# Adafruit_RGB_Matrix_HAT.net
KiCad netlist of a schematic drawn in EAGLE
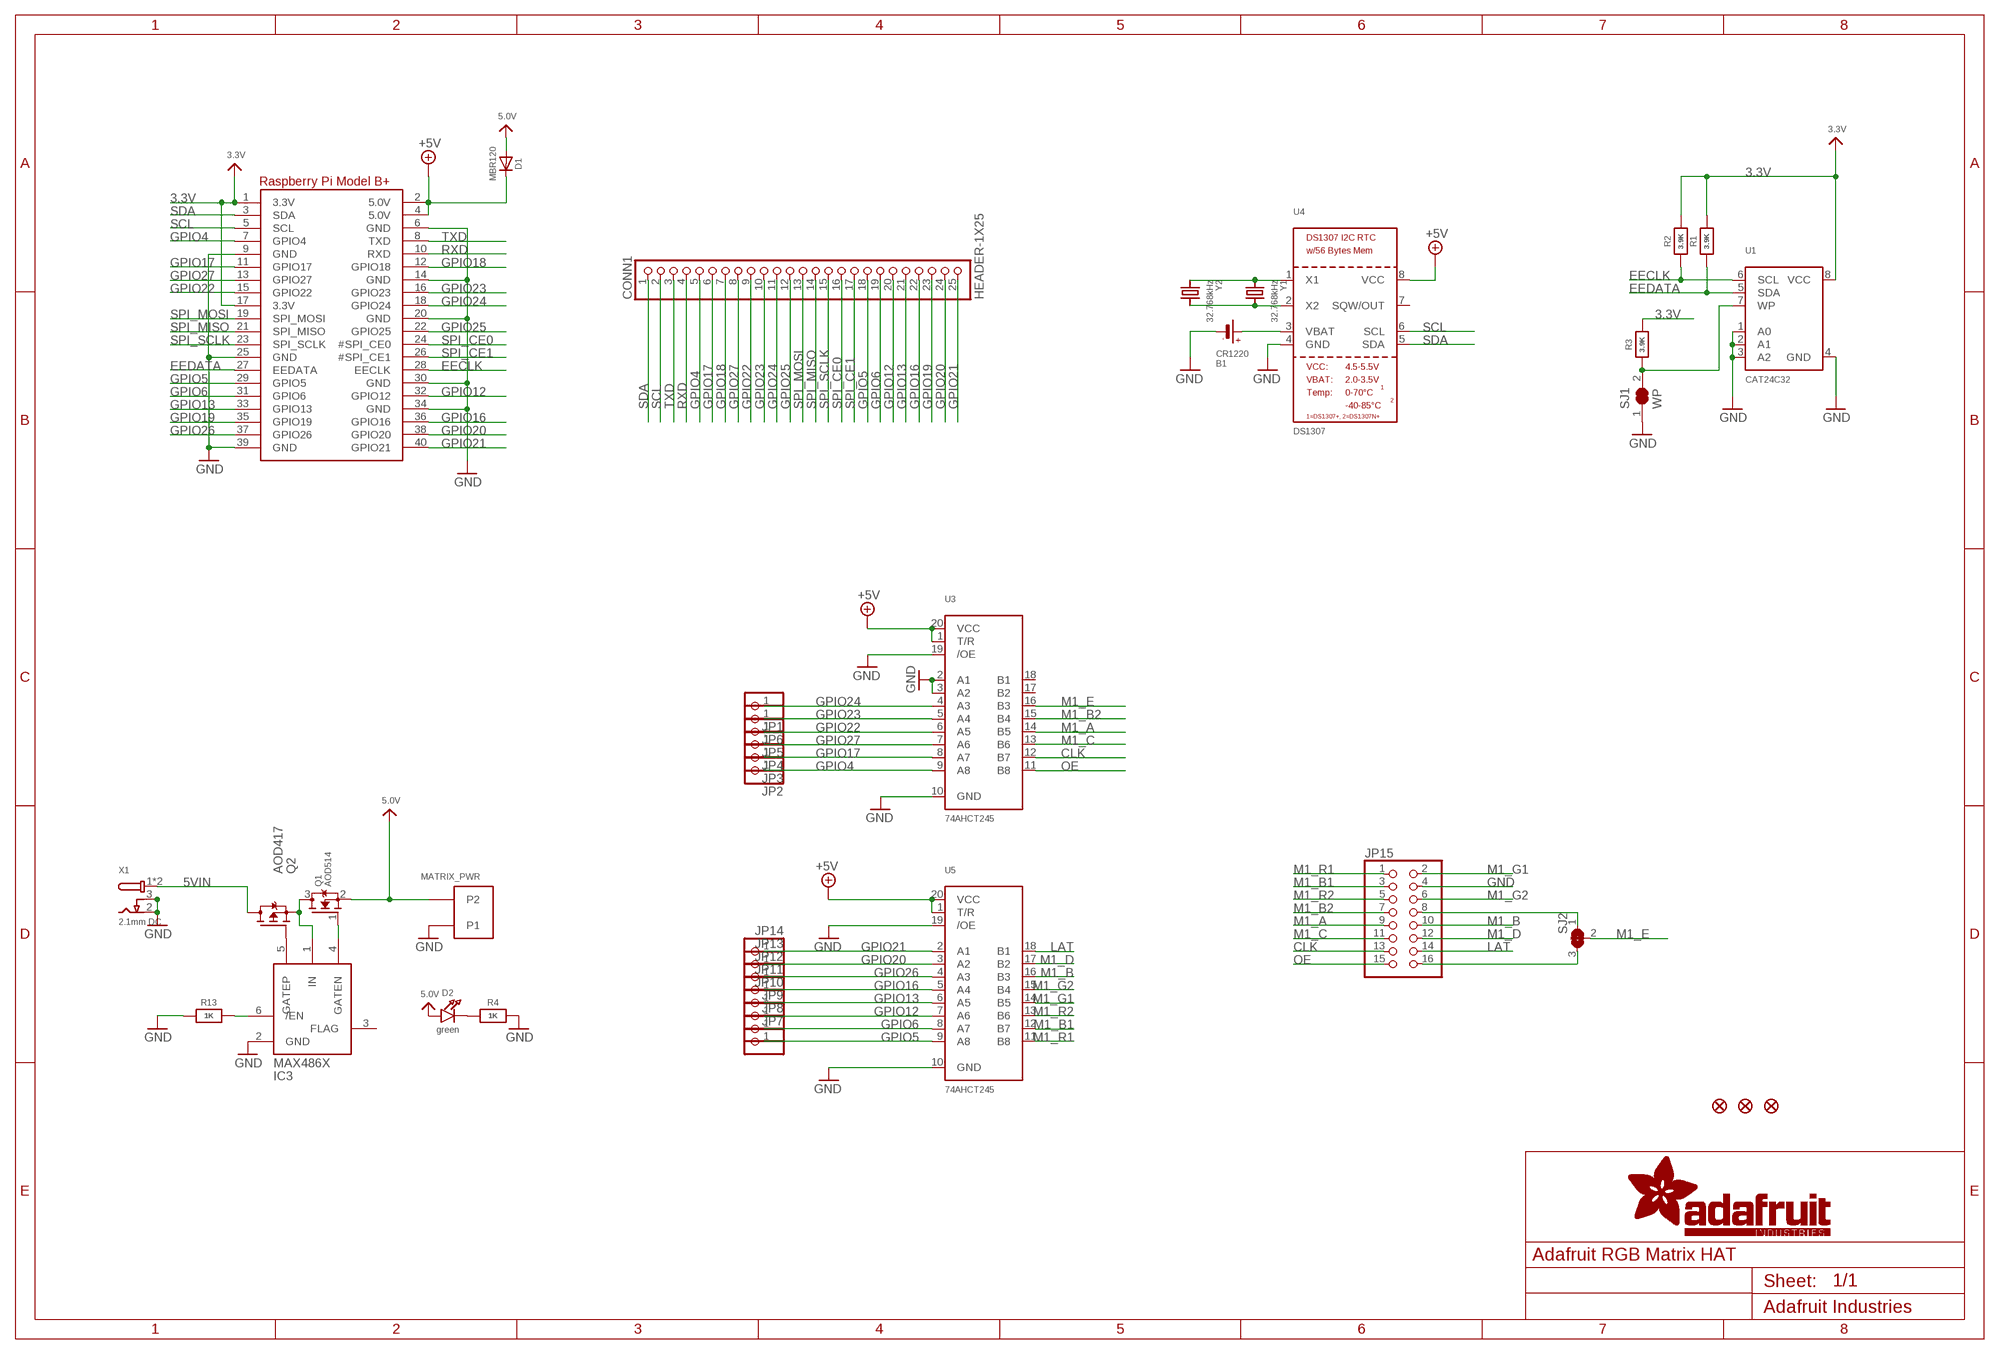
[diagram p0: schematic, sheet 1]

(export (version "E")
  (design (tool "Eeschema 10.0.6"))
  (components
    (comp (ref "B1")
      (value "CR1220")
      (footprint "eagle-import:CR1220")
      (libsource (lib "eagle-import") (part "BATTERYCR1220_SMT"))
    )
    (comp (ref "CONN1")
      (value "HEADER-1X25")
      (footprint "eagle-import:1X25_ROUND_70MIL")
      (libsource (lib "eagle-import") (part "HEADER-1X25"))
    )
    (comp (ref "D1")
      (value "MBR120")
      (footprint "eagle-import:SOD-123")
      (libsource (lib "eagle-import") (part "DIODESOD-123"))
    )
    (comp (ref "D2")
      (value "green")
      (footprint "eagle-import:CHIPLED_0805_NOOUTLINE")
      (libsource (lib "eagle-import") (part "LED0805_NOOUTLINE"))
    )
    (comp (ref "FID1")
      (value "FIDUCIAL_1MM")
      (footprint "eagle-import:FIDUCIAL_1MM")
      (libsource (lib "eagle-import") (part "FIDUCIAL_1MM"))
    )
    (comp (ref "FID2")
      (value "FIDUCIAL_1MM")
      (footprint "eagle-import:FIDUCIAL_1MM")
      (libsource (lib "eagle-import") (part "FIDUCIAL_1MM"))
    )
    (comp (ref "FID3")
      (value "FIDUCIAL_1MM")
      (footprint "eagle-import:FIDUCIAL_1MM")
      (libsource (lib "eagle-import") (part "FIDUCIAL_1MM"))
    )
    (comp (ref "IC3")
      (value "MAX4866T")
      (footprint "eagle-import:SOT23-6")
      (libsource (lib "eagle-import") (part "MAX486X/SOT"))
    )
    (comp (ref "JP1")
      (value "PINHD-1X1")
      (footprint "eagle-import:1X01")
      (libsource (lib "eagle-import") (part "PINHD-1X1"))
    )
    (comp (ref "JP2")
      (value "PINHD-1X1")
      (footprint "eagle-import:1X01")
      (libsource (lib "eagle-import") (part "PINHD-1X1"))
    )
    (comp (ref "JP3")
      (value "PINHD-1X1")
      (footprint "eagle-import:1X01")
      (libsource (lib "eagle-import") (part "PINHD-1X1"))
    )
    (comp (ref "JP4")
      (value "PINHD-1X1")
      (footprint "eagle-import:1X01")
      (libsource (lib "eagle-import") (part "PINHD-1X1"))
    )
    (comp (ref "JP5")
      (value "PINHD-1X1")
      (footprint "eagle-import:1X01")
      (libsource (lib "eagle-import") (part "PINHD-1X1"))
    )
    (comp (ref "JP6")
      (value "PINHD-1X1")
      (footprint "eagle-import:1X01")
      (libsource (lib "eagle-import") (part "PINHD-1X1"))
    )
    (comp (ref "JP7")
      (value "PINHD-1X1")
      (footprint "eagle-import:1X01")
      (libsource (lib "eagle-import") (part "PINHD-1X1"))
    )
    (comp (ref "JP8")
      (value "PINHD-1X1")
      (footprint "eagle-import:1X01")
      (libsource (lib "eagle-import") (part "PINHD-1X1"))
    )
    (comp (ref "JP9")
      (value "PINHD-1X1")
      (footprint "eagle-import:1X01")
      (libsource (lib "eagle-import") (part "PINHD-1X1"))
    )
    (comp (ref "JP10")
      (value "PINHD-1X1")
      (footprint "eagle-import:1X01")
      (libsource (lib "eagle-import") (part "PINHD-1X1"))
    )
    (comp (ref "JP11")
      (value "PINHD-1X1")
      (footprint "eagle-import:1X01")
      (libsource (lib "eagle-import") (part "PINHD-1X1"))
    )
    (comp (ref "JP12")
      (value "PINHD-1X1")
      (footprint "eagle-import:1X01")
      (libsource (lib "eagle-import") (part "PINHD-1X1"))
    )
    (comp (ref "JP13")
      (value "PINHD-1X1")
      (footprint "eagle-import:1X01")
      (libsource (lib "eagle-import") (part "PINHD-1X1"))
    )
    (comp (ref "JP14")
      (value "PINHD-1X1")
      (footprint "eagle-import:1X01")
      (libsource (lib "eagle-import") (part "PINHD-1X1"))
    )
    (comp (ref "JP15")
      (value "HEADER-2X8_SHROUDED")
      (footprint "eagle-import:2X08_SHROUDED")
      (libsource (lib "eagle-import") (part "HEADER-2X8_SHROUDED"))
    )
    (comp (ref "MATRIX_PWR")
      (value "PINHEAD")
      (footprint "eagle-import:TERMBLOCK508")
      (libsource (lib "eagle-import") (part "PINHEAD"))
    )
    (comp (ref "Q1")
      (value "AOD514")
      (footprint "eagle-import:TO252")
      (libsource (lib "eagle-import") (part "MOSFET-N_TO252"))
    )
    (comp (ref "Q2")
      (value "AOD417")
      (footprint "eagle-import:TO252")
      (libsource (lib "eagle-import") (part "MOSFET-PTO252"))
    )
    (comp (ref "R1")
      (value "3.9K")
      (footprint "eagle-import:0805-NO")
      (libsource (lib "eagle-import") (part "RESISTOR0805_NOOUTLINE"))
    )
    (comp (ref "R2")
      (value "3.9K")
      (footprint "eagle-import:0805-NO")
      (libsource (lib "eagle-import") (part "RESISTOR0805_NOOUTLINE"))
    )
    (comp (ref "R3")
      (value "3.9K")
      (footprint "eagle-import:0805-NO")
      (libsource (lib "eagle-import") (part "RESISTOR0805_NOOUTLINE"))
    )
    (comp (ref "R4")
      (value "1K")
      (footprint "eagle-import:0805-NO")
      (libsource (lib "eagle-import") (part "RESISTOR0805_NOOUTLINE"))
    )
    (comp (ref "R13")
      (value "1K")
      (footprint "eagle-import:0805-NO")
      (libsource (lib "eagle-import") (part "RESISTOR0805_NOOUTLINE"))
    )
    (comp (ref "RPI1")
      (value "RASPBERRYPI_BPLUS_HATSLOTS")
      (footprint "eagle-import:PI_HAT_SLOTS")
      (libsource (lib "eagle-import") (part "RASPBERRYPI_BPLUS_HATSLOTS"))
    )
    (comp (ref "SJ1")
      (value "WP")
      (footprint "eagle-import:SOLDERJUMPER_CLOSEDWIRE")
      (libsource (lib "eagle-import") (part "SOLDERJUMPER_CLOSED"))
    )
    (comp (ref "SJ2")
      (value "SOLDERJUMPER_2WAY")
      (footprint "eagle-import:SOLDERJUMPER_2WAY_OPEN_NOPASTE")
      (libsource (lib "eagle-import") (part "SOLDERJUMPER_2WAY"))
    )
    (comp (ref "U1")
      (value "CAT24C32")
      (footprint "eagle-import:SOIC8_150MIL")
      (libsource (lib "eagle-import") (part "EEPROM_I2C_8PIN_GENERIC"))
    )
    (comp (ref "U3")
      (value "74AHCT245")
      (footprint "eagle-import:TSSOP20")
      (libsource (lib "eagle-import") (part "74LCX245_TSSOP20"))
    )
    (comp (ref "U4")
      (value "DS1307")
      (footprint "eagle-import:SOIC8_150MIL")
      (libsource (lib "eagle-import") (part "RTC_DS1307"))
    )
    (comp (ref "U5")
      (value "74AHCT245")
      (footprint "eagle-import:TSSOP20")
      (libsource (lib "eagle-import") (part "74LCX245_TSSOP20"))
    )
    (comp (ref "X1")
      (value "2.1mm DC")
      (footprint "eagle-import:DCJACK_2MM_SMT")
      (libsource (lib "eagle-import") (part "DCBARRELSMT"))
    )
    (comp (ref "Y1")
      (value "32.768kHz")
      (footprint "eagle-import:CRYSTAL_8X3.8")
      (libsource (lib "eagle-import") (part "CRYSTAL8.0X3.8"))
    )
    (comp (ref "Y2")
      (value "32.768kHz")
      (footprint "eagle-import:XTAL3215")
      (libsource (lib "eagle-import") (part "CRYSTAL_3215"))
    )
  )
  (nets
    (net (code "1") (name "+5V") (class "Default")
      (node (ref "D1") (pin "C") (pinfunction "C_C") (pintype "passive"))
      (node (ref "RPI1") (pin "2") (pinfunction "5.0V_2") (pintype "power_in"))
      (node (ref "RPI1") (pin "4") (pinfunction "5.0V_4") (pintype "power_in"))
      (node (ref "U3") (pin "1") (pinfunction "T/R_1") (pintype "bidirectional"))
      (node (ref "U3") (pin "20") (pinfunction "VCC_20") (pintype "bidirectional"))
      (node (ref "U4") (pin "8") (pinfunction "VCC_8") (pintype "bidirectional"))
      (node (ref "U5") (pin "1") (pinfunction "T/R_1") (pintype "bidirectional"))
      (node (ref "U5") (pin "20") (pinfunction "VCC_20") (pintype "bidirectional"))
    )
    (net (code "2") (name "/5VIN") (class "Default")
      (node (ref "Q2") (pin "3") (pinfunction "D_3") (pintype "passive"))
      (node (ref "X1") (pin "1") (pinfunction "PWR_1") (pintype "power_in"))
      (node (ref "X1") (pin "1'") (pinfunction "PWR_1'") (pintype "power_in"))
    )
    (net (code "3") (name "/CLK") (class "Default")
      (node (ref "JP15") (pin "13") (pinfunction "13_13") (pintype "passive"))
      (node (ref "U3") (pin "12") (pinfunction "B7_12") (pintype "bidirectional"))
    )
    (net (code "4") (name "/EECLK") (class "Default")
      (node (ref "R2") (pin "1") (pinfunction "1_1") (pintype "passive"))
      (node (ref "RPI1") (pin "28") (pinfunction "EECLK_28") (pintype "bidirectional"))
      (node (ref "U1") (pin "6") (pinfunction "SCL_6") (pintype "input"))
    )
    (net (code "5") (name "/EEDATA") (class "Default")
      (node (ref "R1") (pin "1") (pinfunction "1_1") (pintype "passive"))
      (node (ref "RPI1") (pin "27") (pinfunction "EEDATA_27") (pintype "bidirectional"))
      (node (ref "U1") (pin "5") (pinfunction "SDA_5") (pintype "bidirectional"))
    )
    (net (code "6") (name "/GPIO4") (class "Default")
      (node (ref "CONN1") (pin "5") (pinfunction "5_5") (pintype "passive"))
      (node (ref "JP2") (pin "1") (pinfunction "1_1") (pintype "passive"))
      (node (ref "RPI1") (pin "7") (pinfunction "GPIO4_7") (pintype "bidirectional"))
      (node (ref "U3") (pin "9") (pinfunction "A8_9") (pintype "bidirectional"))
    )
    (net (code "7") (name "/GPIO5") (class "Default")
      (node (ref "CONN1") (pin "18") (pinfunction "18_18") (pintype "passive"))
      (node (ref "JP7") (pin "1") (pinfunction "1_1") (pintype "passive"))
      (node (ref "RPI1") (pin "29") (pinfunction "GPIO5_29") (pintype "bidirectional"))
      (node (ref "U5") (pin "9") (pinfunction "A8_9") (pintype "bidirectional"))
    )
    (net (code "8") (name "/GPIO6") (class "Default")
      (node (ref "CONN1") (pin "19") (pinfunction "19_19") (pintype "passive"))
      (node (ref "JP8") (pin "1") (pinfunction "1_1") (pintype "passive"))
      (node (ref "RPI1") (pin "31") (pinfunction "GPIO6_31") (pintype "bidirectional"))
      (node (ref "U5") (pin "8") (pinfunction "A7_8") (pintype "bidirectional"))
    )
    (net (code "9") (name "/GPIO12") (class "Default")
      (node (ref "CONN1") (pin "20") (pinfunction "20_20") (pintype "passive"))
      (node (ref "JP9") (pin "1") (pinfunction "1_1") (pintype "passive"))
      (node (ref "RPI1") (pin "32") (pinfunction "GPIO12_32") (pintype "bidirectional"))
      (node (ref "U5") (pin "7") (pinfunction "A6_7") (pintype "bidirectional"))
    )
    (net (code "10") (name "/GPIO13") (class "Default")
      (node (ref "CONN1") (pin "21") (pinfunction "21_21") (pintype "passive"))
      (node (ref "JP10") (pin "1") (pinfunction "1_1") (pintype "passive"))
      (node (ref "RPI1") (pin "33") (pinfunction "GPIO13_33") (pintype "bidirectional"))
      (node (ref "U5") (pin "6") (pinfunction "A5_6") (pintype "bidirectional"))
    )
    (net (code "11") (name "/GPIO16") (class "Default")
      (node (ref "CONN1") (pin "22") (pinfunction "22_22") (pintype "passive"))
      (node (ref "JP11") (pin "1") (pinfunction "1_1") (pintype "passive"))
      (node (ref "RPI1") (pin "36") (pinfunction "GPIO16_36") (pintype "bidirectional"))
      (node (ref "U5") (pin "5") (pinfunction "A4_5") (pintype "bidirectional"))
    )
    (net (code "12") (name "/GPIO17") (class "Default")
      (node (ref "CONN1") (pin "6") (pinfunction "6_6") (pintype "passive"))
      (node (ref "JP3") (pin "1") (pinfunction "1_1") (pintype "passive"))
      (node (ref "RPI1") (pin "11") (pinfunction "GPIO17_11") (pintype "bidirectional"))
      (node (ref "U3") (pin "8") (pinfunction "A7_8") (pintype "bidirectional"))
    )
    (net (code "13") (name "/GPIO18") (class "Default")
      (node (ref "CONN1") (pin "7") (pinfunction "7_7") (pintype "passive"))
      (node (ref "RPI1") (pin "12") (pinfunction "GPIO18_12") (pintype "bidirectional"))
    )
    (net (code "14") (name "/GPIO19") (class "Default")
      (node (ref "CONN1") (pin "23") (pinfunction "23_23") (pintype "passive"))
      (node (ref "RPI1") (pin "35") (pinfunction "GPIO19_35") (pintype "bidirectional"))
    )
    (net (code "15") (name "/GPIO20") (class "Default")
      (node (ref "CONN1") (pin "24") (pinfunction "24_24") (pintype "passive"))
      (node (ref "JP13") (pin "1") (pinfunction "1_1") (pintype "passive"))
      (node (ref "RPI1") (pin "38") (pinfunction "GPIO20_38") (pintype "bidirectional"))
      (node (ref "U5") (pin "3") (pinfunction "A2_3") (pintype "bidirectional"))
    )
    (net (code "16") (name "/GPIO21") (class "Default")
      (node (ref "CONN1") (pin "25") (pinfunction "25_25") (pintype "passive"))
      (node (ref "JP14") (pin "1") (pinfunction "1_1") (pintype "passive"))
      (node (ref "RPI1") (pin "40") (pinfunction "GPIO21_40") (pintype "bidirectional"))
      (node (ref "U5") (pin "2") (pinfunction "A1_2") (pintype "bidirectional"))
    )
    (net (code "17") (name "/GPIO22") (class "Default")
      (node (ref "CONN1") (pin "9") (pinfunction "9_9") (pintype "passive"))
      (node (ref "JP5") (pin "1") (pinfunction "1_1") (pintype "passive"))
      (node (ref "RPI1") (pin "15") (pinfunction "GPIO22_15") (pintype "bidirectional"))
      (node (ref "U3") (pin "6") (pinfunction "A5_6") (pintype "bidirectional"))
    )
    (net (code "18") (name "/GPIO23") (class "Default")
      (node (ref "CONN1") (pin "10") (pinfunction "10_10") (pintype "passive"))
      (node (ref "JP6") (pin "1") (pinfunction "1_1") (pintype "passive"))
      (node (ref "RPI1") (pin "16") (pinfunction "GPIO23_16") (pintype "bidirectional"))
      (node (ref "U3") (pin "5") (pinfunction "A4_5") (pintype "bidirectional"))
    )
    (net (code "19") (name "/GPIO24") (class "Default")
      (node (ref "CONN1") (pin "11") (pinfunction "11_11") (pintype "passive"))
      (node (ref "JP1") (pin "1") (pinfunction "1_1") (pintype "passive"))
      (node (ref "RPI1") (pin "18") (pinfunction "GPIO24_18") (pintype "bidirectional"))
      (node (ref "U3") (pin "4") (pinfunction "A3_4") (pintype "bidirectional"))
    )
    (net (code "20") (name "/GPIO25") (class "Default")
      (node (ref "CONN1") (pin "12") (pinfunction "12_12") (pintype "passive"))
      (node (ref "RPI1") (pin "22") (pinfunction "GPIO25_22") (pintype "bidirectional"))
    )
    (net (code "21") (name "/GPIO26") (class "Default")
      (node (ref "JP12") (pin "1") (pinfunction "1_1") (pintype "passive"))
      (node (ref "RPI1") (pin "37") (pinfunction "GPIO26_37") (pintype "bidirectional"))
      (node (ref "U5") (pin "4") (pinfunction "A3_4") (pintype "bidirectional"))
    )
    (net (code "22") (name "/GPIO27") (class "Default")
      (node (ref "CONN1") (pin "8") (pinfunction "8_8") (pintype "passive"))
      (node (ref "JP4") (pin "1") (pinfunction "1_1") (pintype "passive"))
      (node (ref "RPI1") (pin "13") (pinfunction "GPIO27_13") (pintype "bidirectional"))
      (node (ref "U3") (pin "7") (pinfunction "A6_7") (pintype "bidirectional"))
    )
    (net (code "23") (name "/LAT") (class "Default")
      (node (ref "JP15") (pin "14") (pinfunction "14_14") (pintype "passive"))
      (node (ref "U5") (pin "18") (pinfunction "B1_18") (pintype "bidirectional"))
    )
    (net (code "24") (name "/M1_A") (class "Default")
      (node (ref "JP15") (pin "9") (pinfunction "9_9") (pintype "passive"))
      (node (ref "U3") (pin "14") (pinfunction "B5_14") (pintype "bidirectional"))
    )
    (net (code "25") (name "/M1_B") (class "Default")
      (node (ref "JP15") (pin "10") (pinfunction "10_10") (pintype "passive"))
      (node (ref "U5") (pin "16") (pinfunction "B3_16") (pintype "bidirectional"))
    )
    (net (code "26") (name "/M1_B1") (class "Default")
      (node (ref "JP15") (pin "3") (pinfunction "3_3") (pintype "passive"))
      (node (ref "U5") (pin "12") (pinfunction "B7_12") (pintype "bidirectional"))
    )
    (net (code "27") (name "/M1_B2") (class "Default")
      (node (ref "JP15") (pin "7") (pinfunction "7_7") (pintype "passive"))
      (node (ref "U3") (pin "15") (pinfunction "B4_15") (pintype "bidirectional"))
    )
    (net (code "28") (name "/M1_C") (class "Default")
      (node (ref "JP15") (pin "11") (pinfunction "11_11") (pintype "passive"))
      (node (ref "U3") (pin "13") (pinfunction "B6_13") (pintype "bidirectional"))
    )
    (net (code "29") (name "/M1_D") (class "Default")
      (node (ref "JP15") (pin "12") (pinfunction "12_12") (pintype "passive"))
      (node (ref "U5") (pin "17") (pinfunction "B2_17") (pintype "bidirectional"))
    )
    (net (code "30") (name "/M1_E") (class "Default")
      (node (ref "SJ2") (pin "2") (pinfunction "2_2") (pintype "passive"))
      (node (ref "U3") (pin "16") (pinfunction "B3_16") (pintype "bidirectional"))
    )
    (net (code "31") (name "/M1_G1") (class "Default")
      (node (ref "JP15") (pin "2") (pinfunction "2_2") (pintype "passive"))
      (node (ref "U5") (pin "14") (pinfunction "B5_14") (pintype "bidirectional"))
    )
    (net (code "32") (name "/M1_G2") (class "Default")
      (node (ref "JP15") (pin "6") (pinfunction "6_6") (pintype "passive"))
      (node (ref "U5") (pin "15") (pinfunction "B4_15") (pintype "bidirectional"))
    )
    (net (code "33") (name "/M1_R1") (class "Default")
      (node (ref "JP15") (pin "1") (pinfunction "1_1") (pintype "passive"))
      (node (ref "U5") (pin "11") (pinfunction "B8_11") (pintype "bidirectional"))
    )
    (net (code "34") (name "/M1_R2") (class "Default")
      (node (ref "JP15") (pin "5") (pinfunction "5_5") (pintype "passive"))
      (node (ref "U5") (pin "13") (pinfunction "B6_13") (pintype "bidirectional"))
    )
    (net (code "35") (name "/OE") (class "Default")
      (node (ref "JP15") (pin "15") (pinfunction "15_15") (pintype "passive"))
      (node (ref "U3") (pin "11") (pinfunction "B8_11") (pintype "bidirectional"))
    )
    (net (code "36") (name "/RXD") (class "Default")
      (node (ref "CONN1") (pin "4") (pinfunction "4_4") (pintype "passive"))
      (node (ref "RPI1") (pin "10") (pinfunction "RXD_10") (pintype "bidirectional"))
    )
    (net (code "37") (name "/SCL") (class "Default")
      (node (ref "CONN1") (pin "2") (pinfunction "2_2") (pintype "passive"))
      (node (ref "RPI1") (pin "5") (pinfunction "SCL_5") (pintype "bidirectional"))
      (node (ref "U4") (pin "6") (pinfunction "SCL_6") (pintype "bidirectional"))
    )
    (net (code "38") (name "/SDA") (class "Default")
      (node (ref "CONN1") (pin "1") (pinfunction "1_1") (pintype "passive"))
      (node (ref "RPI1") (pin "3") (pinfunction "SDA_3") (pintype "bidirectional"))
      (node (ref "U4") (pin "5") (pinfunction "SDA_5") (pintype "bidirectional"))
    )
    (net (code "39") (name "/SPI_CE0") (class "Default")
      (node (ref "CONN1") (pin "16") (pinfunction "16_16") (pintype "passive"))
      (node (ref "RPI1") (pin "24") (pinfunction "#SPI_CE0_24") (pintype "bidirectional"))
    )
    (net (code "40") (name "/SPI_CE1") (class "Default")
      (node (ref "CONN1") (pin "17") (pinfunction "17_17") (pintype "passive"))
      (node (ref "RPI1") (pin "26") (pinfunction "#SPI_CE1_26") (pintype "bidirectional"))
    )
    (net (code "41") (name "/SPI_MISO") (class "Default")
      (node (ref "CONN1") (pin "14") (pinfunction "14_14") (pintype "passive"))
      (node (ref "RPI1") (pin "21") (pinfunction "SPI_MISO_21") (pintype "bidirectional"))
    )
    (net (code "42") (name "/SPI_MOSI") (class "Default")
      (node (ref "CONN1") (pin "13") (pinfunction "13_13") (pintype "passive"))
      (node (ref "RPI1") (pin "19") (pinfunction "SPI_MOSI_19") (pintype "bidirectional"))
    )
    (net (code "43") (name "/SPI_SCLK") (class "Default")
      (node (ref "CONN1") (pin "15") (pinfunction "15_15") (pintype "passive"))
      (node (ref "RPI1") (pin "23") (pinfunction "SPI_SCLK_23") (pintype "bidirectional"))
    )
    (net (code "44") (name "/TXD") (class "Default")
      (node (ref "CONN1") (pin "3") (pinfunction "3_3") (pintype "passive"))
      (node (ref "RPI1") (pin "8") (pinfunction "TXD_8") (pintype "bidirectional"))
    )
    (net (code "45") (name "3.3V") (class "Default")
      (node (ref "R1") (pin "2") (pinfunction "2_2") (pintype "passive"))
      (node (ref "R2") (pin "2") (pinfunction "2_2") (pintype "passive"))
      (node (ref "R3") (pin "2") (pinfunction "2_2") (pintype "passive"))
      (node (ref "RPI1") (pin "1") (pinfunction "3.3V_1") (pintype "power_in"))
      (node (ref "RPI1") (pin "17") (pinfunction "3.3V_17") (pintype "power_in"))
      (node (ref "U1") (pin "8") (pinfunction "VCC_8") (pintype "power_in"))
    )
    (net (code "46") (name "5.0V") (class "Default")
      (node (ref "D1") (pin "A") (pinfunction "A_A") (pintype "passive"))
      (node (ref "D2") (pin "A") (pinfunction "A_A") (pintype "passive"))
      (node (ref "MATRIX_PWR") (pin "P$4") (pinfunction "P2_P$4") (pintype "bidirectional"))
      (node (ref "Q1") (pin "2") (pinfunction "S_2") (pintype "bidirectional"))
    )
    (net (code "47") (name "GND") (class "Default")
      (node (ref "B1") (pin "-") (pinfunction "-_-") (pintype "passive"))
      (node (ref "IC3") (pin "2") (pinfunction "GND_2") (pintype "power_in"))
      (node (ref "JP15") (pin "4") (pinfunction "4_4") (pintype "passive"))
      (node (ref "MATRIX_PWR") (pin "P$3") (pinfunction "P1_P$3") (pintype "bidirectional"))
      (node (ref "R13") (pin "1") (pinfunction "1_1") (pintype "passive"))
      (node (ref "R4") (pin "2") (pinfunction "2_2") (pintype "passive"))
      (node (ref "RPI1") (pin "14") (pinfunction "GND_14") (pintype "power_in"))
      (node (ref "RPI1") (pin "20") (pinfunction "GND_20") (pintype "power_in"))
      (node (ref "RPI1") (pin "25") (pinfunction "GND_25") (pintype "power_in"))
      (node (ref "RPI1") (pin "30") (pinfunction "GND_30") (pintype "power_in"))
      (node (ref "RPI1") (pin "34") (pinfunction "GND_34") (pintype "power_in"))
      (node (ref "RPI1") (pin "39") (pinfunction "GND_39") (pintype "power_in"))
      (node (ref "RPI1") (pin "6") (pinfunction "GND_6") (pintype "power_in"))
      (node (ref "RPI1") (pin "9") (pinfunction "GND_9") (pintype "power_in"))
      (node (ref "SJ1") (pin "1") (pinfunction "1_1") (pintype "passive"))
      (node (ref "U1") (pin "1") (pinfunction "A0_1") (pintype "input"))
      (node (ref "U1") (pin "2") (pinfunction "A1_2") (pintype "input"))
      (node (ref "U1") (pin "3") (pinfunction "A2_3") (pintype "input"))
      (node (ref "U1") (pin "4") (pinfunction "GND_4") (pintype "power_in"))
      (node (ref "U3") (pin "10") (pinfunction "GND_10") (pintype "bidirectional"))
      (node (ref "U3") (pin "19") (pinfunction "/OE_19") (pintype "bidirectional"))
      (node (ref "U3") (pin "2") (pinfunction "A1_2") (pintype "bidirectional"))
      (node (ref "U3") (pin "3") (pinfunction "A2_3") (pintype "bidirectional"))
      (node (ref "U4") (pin "4") (pinfunction "GND_4") (pintype "bidirectional"))
      (node (ref "U5") (pin "10") (pinfunction "GND_10") (pintype "bidirectional"))
      (node (ref "U5") (pin "19") (pinfunction "/OE_19") (pintype "bidirectional"))
      (node (ref "X1") (pin "2") (pinfunction "GND_2") (pintype "power_in"))
      (node (ref "X1") (pin "3") (pinfunction "GNDBREAK_3") (pintype "power_in"))
    )
    (net (code "48") (name "Net-(D2-PadC)") (class "Default")
      (node (ref "D2") (pin "C") (pinfunction "C_C") (pintype "passive"))
      (node (ref "R4") (pin "1") (pinfunction "1_1") (pintype "passive"))
    )
    (net (code "49") (name "Net-(IC3-GATEN)") (class "Default")
      (node (ref "IC3") (pin "4") (pinfunction "GATEN_4") (pintype "output"))
      (node (ref "Q1") (pin "1") (pinfunction "G_1") (pintype "bidirectional"))
    )
    (net (code "50") (name "Net-(IC3-GATEP)") (class "Default")
      (node (ref "IC3") (pin "5") (pinfunction "GATEP_5") (pintype "output"))
      (node (ref "Q2") (pin "1") (pinfunction "G_1") (pintype "passive"))
    )
    (net (code "51") (name "Net-(IC3-IN)") (class "Default")
      (node (ref "IC3") (pin "1") (pinfunction "IN_1") (pintype "input"))
      (node (ref "Q1") (pin "3") (pinfunction "D_3") (pintype "bidirectional"))
      (node (ref "Q2") (pin "2") (pinfunction "S_2") (pintype "passive"))
    )
    (net (code "52") (name "Net-(IC3-{slash}EN)") (class "Default")
      (node (ref "IC3") (pin "6") (pinfunction "/EN_6") (pintype "input"))
      (node (ref "R13") (pin "2") (pinfunction "2_2") (pintype "passive"))
    )
    (net (code "53") (name "Net-(JP15-Pad8)") (class "Default")
      (node (ref "JP15") (pin "8") (pinfunction "8_8") (pintype "passive"))
      (node (ref "SJ2") (pin "1") (pinfunction "1_1") (pintype "passive"))
    )
    (net (code "54") (name "Net-(JP15-Pad16)") (class "Default")
      (node (ref "JP15") (pin "16") (pinfunction "16_16") (pintype "passive"))
      (node (ref "SJ2") (pin "3") (pinfunction "3_3") (pintype "passive"))
    )
    (net (code "55") (name "Net-(U1-WP)") (class "Default")
      (node (ref "R3") (pin "1") (pinfunction "1_1") (pintype "passive"))
      (node (ref "SJ1") (pin "2") (pinfunction "2_2") (pintype "passive"))
      (node (ref "U1") (pin "7") (pinfunction "WP_7") (pintype "input"))
    )
    (net (code "56") (name "Net-(U4-VBAT)") (class "Default")
      (node (ref "B1") (pin "+$1") (pinfunction "+_+$1") (pintype "passive"))
      (node (ref "B1") (pin "+$2") (pinfunction "+_+$2") (pintype "passive"))
      (node (ref "U4") (pin "3") (pinfunction "VBAT_3") (pintype "bidirectional"))
    )
    (net (code "57") (name "Net-(U4-X1)") (class "Default")
      (node (ref "U4") (pin "1") (pinfunction "X1_1") (pintype "bidirectional"))
      (node (ref "Y1") (pin "P$1") (pinfunction "1_P$1") (pintype "passive"))
      (node (ref "Y2") (pin "P$1") (pinfunction "1_P$1") (pintype "passive"))
    )
    (net (code "58") (name "Net-(U4-X2)") (class "Default")
      (node (ref "U4") (pin "2") (pinfunction "X2_2") (pintype "bidirectional"))
      (node (ref "Y1") (pin "P$4") (pinfunction "2_P$4") (pintype "passive"))
      (node (ref "Y2") (pin "P$2") (pinfunction "2_P$2") (pintype "passive"))
    )
    (net (code "59") (name "unconnected-(IC3-FLAG-Pad3)") (class "Default")
      (node (ref "IC3") (pin "3") (pinfunction "FLAG_3") (pintype "output"))
    )
    (net (code "60") (name "unconnected-(U3-B1-Pad18)") (class "Default")
      (node (ref "U3") (pin "18") (pinfunction "B1_18") (pintype "bidirectional"))
    )
    (net (code "61") (name "unconnected-(U3-B2-Pad17)") (class "Default")
      (node (ref "U3") (pin "17") (pinfunction "B2_17") (pintype "bidirectional"))
    )
    (net (code "62") (name "unconnected-(U4-SQW{slash}OUT-Pad7)") (class "Default")
      (node (ref "U4") (pin "7") (pinfunction "SQW/OUT_7") (pintype "bidirectional"))
    )
  )
)
